# MonitorOut.net
KiCad netlist of a schematic drawn in Altium Designer
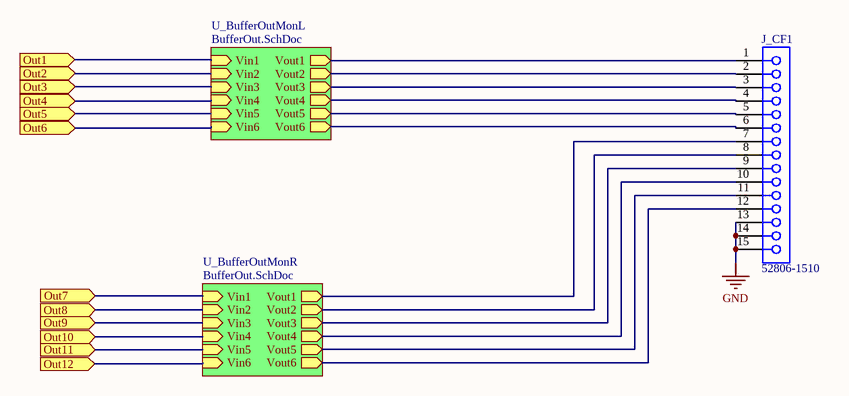
[diagram p0: MonitorOut.SchDoc]

(export (version "E")
  (design (tool "Eeschema 10.0.6"))
  (components
    (comp (ref "J_CF1")
      (value "52806-1510")
      (footprint "MOLX-52806-1510")
      (fields (field (name "MANUFACTURER") "Molex"))
      (libsource (lib "Altium Content Vault") (part "MOLX-52806-1510"))
    )
  )
  (nets
    (net (code "13") (name "/Vout1") (class "Default")
      (node (ref "J_CF1") (pin "1") (pinfunction "1_1") (pintype "passive"))
    )
    (net (code "14") (name "/Vout1_1") (class "Default")
      (node (ref "J_CF1") (pin "7") (pinfunction "7_7") (pintype "passive"))
    )
    (net (code "15") (name "/Vout2") (class "Default")
      (node (ref "J_CF1") (pin "2") (pinfunction "2_2") (pintype "passive"))
    )
    (net (code "16") (name "/Vout2_1") (class "Default")
      (node (ref "J_CF1") (pin "8") (pinfunction "8_8") (pintype "passive"))
    )
    (net (code "17") (name "/Vout3") (class "Default")
      (node (ref "J_CF1") (pin "3") (pinfunction "3_3") (pintype "passive"))
    )
    (net (code "18") (name "/Vout3_1") (class "Default")
      (node (ref "J_CF1") (pin "9") (pinfunction "9_9") (pintype "passive"))
    )
    (net (code "19") (name "/Vout4") (class "Default")
      (node (ref "J_CF1") (pin "4") (pinfunction "4_4") (pintype "passive"))
    )
    (net (code "20") (name "/Vout4_1") (class "Default")
      (node (ref "J_CF1") (pin "10") (pinfunction "10_10") (pintype "passive"))
    )
    (net (code "21") (name "/Vout5") (class "Default")
      (node (ref "J_CF1") (pin "5") (pinfunction "5_5") (pintype "passive"))
    )
    (net (code "22") (name "/Vout5_1") (class "Default")
      (node (ref "J_CF1") (pin "11") (pinfunction "11_11") (pintype "passive"))
    )
    (net (code "23") (name "/Vout6") (class "Default")
      (node (ref "J_CF1") (pin "6") (pinfunction "6_6") (pintype "passive"))
    )
    (net (code "24") (name "/Vout6_1") (class "Default")
      (node (ref "J_CF1") (pin "12") (pinfunction "12_12") (pintype "passive"))
    )
    (net (code "25") (name "GND") (class "Default")
      (node (ref "J_CF1") (pin "13") (pinfunction "13_13") (pintype "passive"))
      (node (ref "J_CF1") (pin "14") (pinfunction "14_14") (pintype "passive"))
      (node (ref "J_CF1") (pin "15") (pinfunction "15_15") (pintype "passive"))
    )
  )
)
